# Gimbal_Driveboard.net
KiCad netlist of a schematic drawn in EAGLE
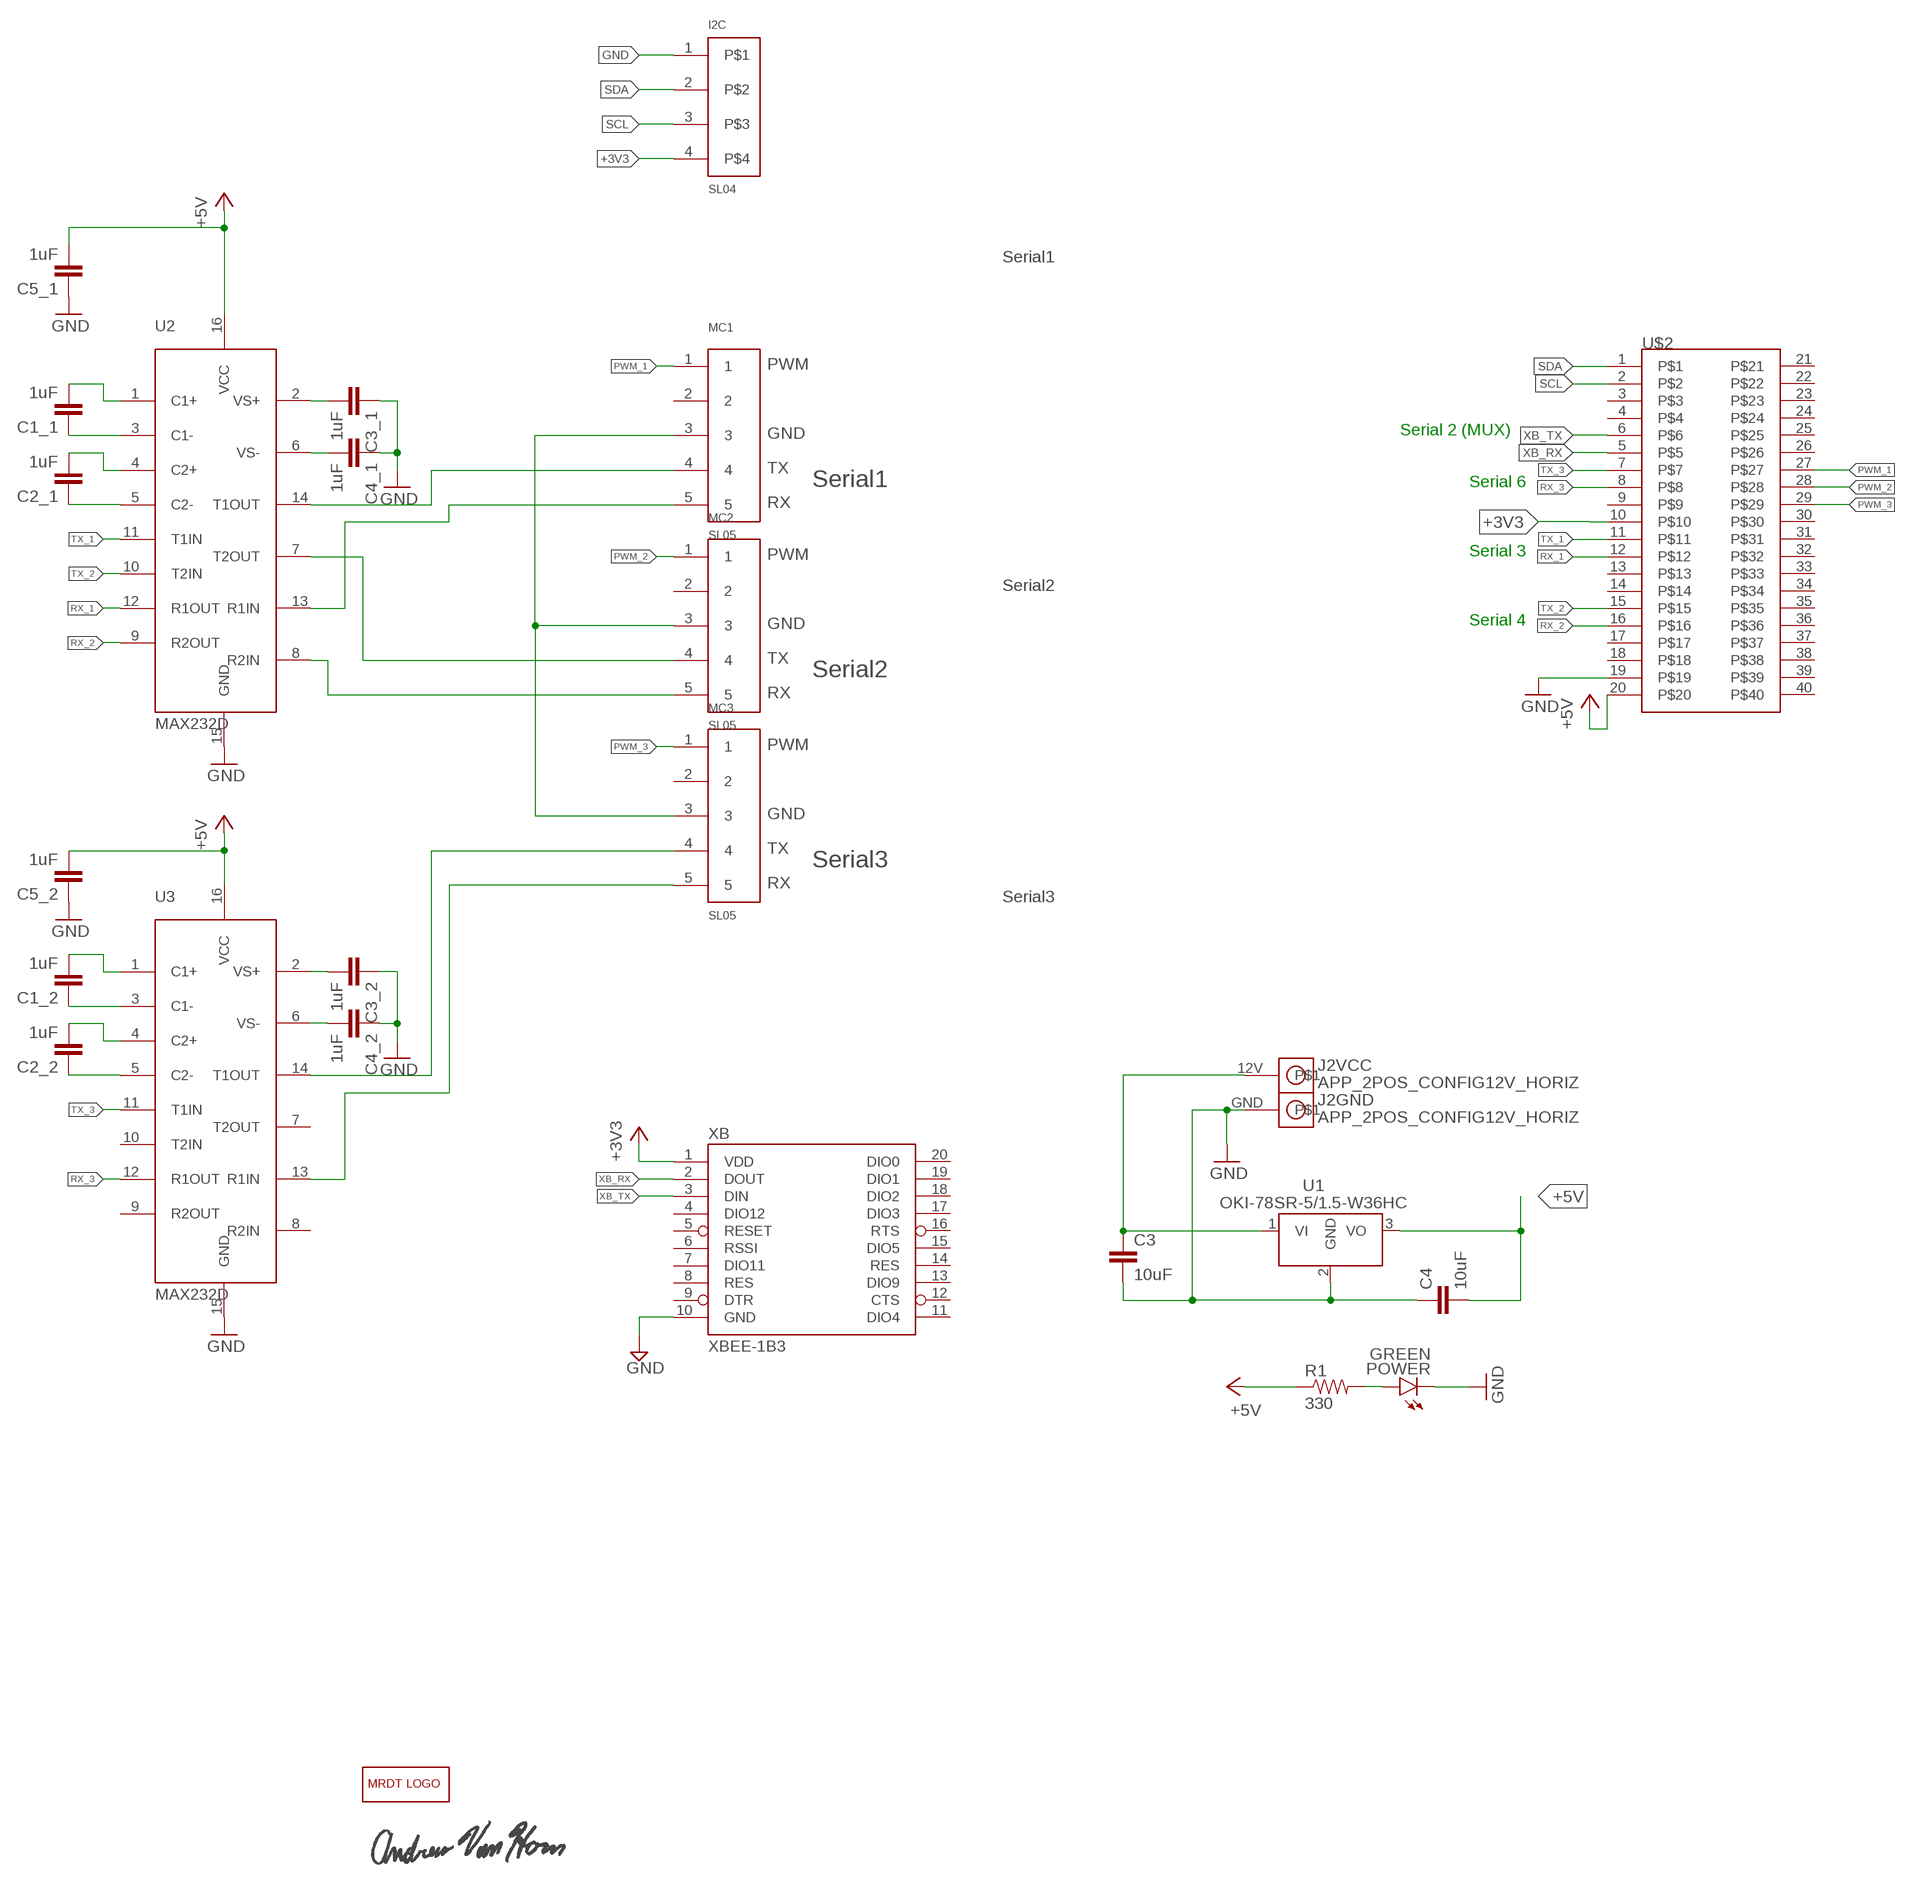
[diagram p0: schematic, sheet 1]

(export (version "E")
  (design (tool "Eeschema 10.0.6"))
  (components
    (comp (ref "C1_1")
      (value "1uF")
      (footprint "eagle-import:0805")
      (libsource (lib "eagle-import") (part "CAP0805"))
    )
    (comp (ref "C1_2")
      (value "1uF")
      (footprint "eagle-import:0805")
      (libsource (lib "eagle-import") (part "CAP0805"))
    )
    (comp (ref "C2_1")
      (value "1uF")
      (footprint "eagle-import:0805")
      (libsource (lib "eagle-import") (part "CAP0805"))
    )
    (comp (ref "C2_2")
      (value "1uF")
      (footprint "eagle-import:0805")
      (libsource (lib "eagle-import") (part "CAP0805"))
    )
    (comp (ref "C3")
      (value "10uF")
      (footprint "eagle-import:0805")
      (libsource (lib "eagle-import") (part "CAP0805"))
    )
    (comp (ref "C3_1")
      (value "1uF")
      (footprint "eagle-import:0805")
      (libsource (lib "eagle-import") (part "CAP0805"))
    )
    (comp (ref "C3_2")
      (value "1uF")
      (footprint "eagle-import:0805")
      (libsource (lib "eagle-import") (part "CAP0805"))
    )
    (comp (ref "C4")
      (value "10uF")
      (footprint "eagle-import:0805")
      (libsource (lib "eagle-import") (part "CAP0805"))
    )
    (comp (ref "C4_1")
      (value "1uF")
      (footprint "eagle-import:0805")
      (libsource (lib "eagle-import") (part "CAP0805"))
    )
    (comp (ref "C4_2")
      (value "1uF")
      (footprint "eagle-import:0805")
      (libsource (lib "eagle-import") (part "CAP0805"))
    )
    (comp (ref "C5_1")
      (value "1uF")
      (footprint "eagle-import:0805")
      (libsource (lib "eagle-import") (part "CAP0805"))
    )
    (comp (ref "C5_2")
      (value "1uF")
      (footprint "eagle-import:0805")
      (libsource (lib "eagle-import") (part "CAP0805"))
    )
    (comp (ref "I2C")
      (value "SL04")
      (footprint "eagle-import:MOLEX_SL_04_TH")
      (libsource (lib "eagle-import") (part "SL04"))
    )
    (comp (ref "J2")
      (value "APP_2POS_CONFIG12V_HORIZ")
      (footprint "eagle-import:APP45_12V_HORIZ_CONFIG")
      (libsource (lib "eagle-import") (part "APP_2POS_CONFIG12V_HORIZ"))
    )
    (comp (ref "LOGO1")
      (value "MRDT_LOGO")
      (footprint "eagle-import:MRDT_LOGO")
      (libsource (lib "eagle-import") (part "MRDT_LOGO"))
    )
    (comp (ref "MC1")
      (value "SL05")
      (footprint "eagle-import:MOLEX_SL_05_TH")
      (libsource (lib "eagle-import") (part "SL05"))
    )
    (comp (ref "MC2")
      (value "SL05")
      (footprint "eagle-import:MOLEX_SL_05_TH")
      (libsource (lib "eagle-import") (part "SL05"))
    )
    (comp (ref "MC3")
      (value "SL05")
      (footprint "eagle-import:MOLEX_SL_05_TH")
      (libsource (lib "eagle-import") (part "SL05"))
    )
    (comp (ref "POWER")
      (value "GREEN")
      (footprint "eagle-import:LED-1206")
      (libsource (lib "eagle-import") (part "LED-GREEN1206"))
    )
    (comp (ref "R1")
      (value "330")
      (footprint "eagle-import:0805")
      (libsource (lib "eagle-import") (part "0.22OHM-1/4W-1%(0805)"))
    )
    (comp (ref "U$2")
      (value "TI_BACKPACK_HEADER")
      (footprint "eagle-import:TI_BACKPACK_HEADER")
      (libsource (lib "eagle-import") (part "TI_BACKPACK_HEADER"))
    )
    (comp (ref "U$3")
      (value "ANDREW_VAN_HORN_SIGNATURE")
      (footprint "eagle-import:ANDREW_VAN_HORN_SIGNATURE")
      (libsource (lib "eagle-import") (part "ANDREW_VAN_HORN_SIGNATURE"))
    )
    (comp (ref "U1")
      (value "OKI-78SR-5/1.5-W36HC")
      (footprint "eagle-import:OKI-78SR_HORIZ")
      (libsource (lib "eagle-import") (part "OKI-78SR-/1.5-W36?CH5"))
    )
    (comp (ref "U2")
      (value "MAX232D")
      (footprint "eagle-import:SOIC16")
      (libsource (lib "eagle-import") (part "MAX232D"))
    )
    (comp (ref "U3")
      (value "MAX232D")
      (footprint "eagle-import:SOIC16")
      (libsource (lib "eagle-import") (part "MAX232D"))
    )
    (comp (ref "XB")
      (value "XBEE-1B3")
      (footprint "eagle-import:XBEE-SMD")
      (libsource (lib "eagle-import") (part "XBEE-1B3"))
    )
  )
  (nets
    (net (code "1") (name "+3V3") (class "Default")
      (node (ref "I2C") (pin "4") (pinfunction "P$4_4") (pintype "bidirectional"))
      (node (ref "U$2") (pin "10") (pinfunction "P$10_10") (pintype "bidirectional"))
      (node (ref "XB") (pin "1") (pinfunction "VDD_1") (pintype "power_in"))
    )
    (net (code "2") (name "+5V") (class "Default")
      (node (ref "C4") (pin "2") (pinfunction "2_2") (pintype "passive"))
      (node (ref "C5_1") (pin "2") (pinfunction "2_2") (pintype "passive"))
      (node (ref "C5_2") (pin "2") (pinfunction "2_2") (pintype "passive"))
      (node (ref "R1") (pin "1") (pinfunction "1_1") (pintype "passive"))
      (node (ref "U$2") (pin "20") (pinfunction "P$20_20") (pintype "bidirectional"))
      (node (ref "U1") (pin "3") (pinfunction "VO_3") (pintype "bidirectional"))
      (node (ref "U2") (pin "16") (pinfunction "VCC_16") (pintype "bidirectional"))
      (node (ref "U3") (pin "16") (pinfunction "VCC_16") (pintype "bidirectional"))
    )
    (net (code "3") (name "GND") (class "Default")
      (node (ref "C3") (pin "2") (pinfunction "2_2") (pintype "passive"))
      (node (ref "C3_1") (pin "1") (pinfunction "1_1") (pintype "passive"))
      (node (ref "C3_2") (pin "1") (pinfunction "1_1") (pintype "passive"))
      (node (ref "C4") (pin "1") (pinfunction "1_1") (pintype "passive"))
      (node (ref "C4_1") (pin "1") (pinfunction "1_1") (pintype "passive"))
      (node (ref "C4_2") (pin "1") (pinfunction "1_1") (pintype "passive"))
      (node (ref "C5_1") (pin "1") (pinfunction "1_1") (pintype "passive"))
      (node (ref "C5_2") (pin "1") (pinfunction "1_1") (pintype "passive"))
      (node (ref "I2C") (pin "1") (pinfunction "P$1_1") (pintype "bidirectional"))
      (node (ref "J2") (pin "GND") (pinfunction "P$1_GND") (pintype "bidirectional"))
      (node (ref "MC1") (pin "3") (pinfunction "3_3") (pintype "bidirectional"))
      (node (ref "MC2") (pin "3") (pinfunction "3_3") (pintype "bidirectional"))
      (node (ref "MC3") (pin "3") (pinfunction "3_3") (pintype "bidirectional"))
      (node (ref "POWER") (pin "C") (pinfunction "C_C") (pintype "passive"))
      (node (ref "U$2") (pin "19") (pinfunction "P$19_19") (pintype "bidirectional"))
      (node (ref "U1") (pin "2") (pinfunction "GND_2") (pintype "bidirectional"))
      (node (ref "U2") (pin "15") (pinfunction "GND_15") (pintype "bidirectional"))
      (node (ref "U3") (pin "15") (pinfunction "GND_15") (pintype "bidirectional"))
      (node (ref "XB") (pin "10") (pinfunction "GND_10") (pintype "power_in"))
    )
    (net (code "4") (name "Net-(J2B-P$1)") (class "Default")
      (node (ref "C3") (pin "1") (pinfunction "1_1") (pintype "passive"))
      (node (ref "J2") (pin "12V") (pinfunction "P$1_12V") (pintype "bidirectional"))
      (node (ref "U1") (pin "1") (pinfunction "VI_1") (pintype "bidirectional"))
    )
    (net (code "5") (name "Net-(POWER-PadA)") (class "Default")
      (node (ref "POWER") (pin "A") (pinfunction "A_A") (pintype "passive"))
      (node (ref "R1") (pin "2") (pinfunction "2_2") (pintype "passive"))
    )
    (net (code "6") (name "Net-(U2-C1+)") (class "Default")
      (node (ref "C1_1") (pin "2") (pinfunction "2_2") (pintype "passive"))
      (node (ref "U2") (pin "1") (pinfunction "C1+_1") (pintype "bidirectional"))
    )
    (net (code "7") (name "Net-(U2-C1-)") (class "Default")
      (node (ref "C1_1") (pin "1") (pinfunction "1_1") (pintype "passive"))
      (node (ref "U2") (pin "3") (pinfunction "C1-_3") (pintype "bidirectional"))
    )
    (net (code "8") (name "Net-(U2-C2+)") (class "Default")
      (node (ref "C2_1") (pin "2") (pinfunction "2_2") (pintype "passive"))
      (node (ref "U2") (pin "4") (pinfunction "C2+_4") (pintype "bidirectional"))
    )
    (net (code "9") (name "Net-(U2-C2-)") (class "Default")
      (node (ref "C2_1") (pin "1") (pinfunction "1_1") (pintype "passive"))
      (node (ref "U2") (pin "5") (pinfunction "C2-_5") (pintype "bidirectional"))
    )
    (net (code "10") (name "Net-(U2-R1IN)") (class "Default")
      (node (ref "MC1") (pin "5") (pinfunction "5_5") (pintype "bidirectional"))
      (node (ref "U2") (pin "13") (pinfunction "R1IN_13") (pintype "bidirectional"))
    )
    (net (code "11") (name "Net-(U2-R2IN)") (class "Default")
      (node (ref "MC2") (pin "5") (pinfunction "5_5") (pintype "bidirectional"))
      (node (ref "U2") (pin "8") (pinfunction "R2IN_8") (pintype "bidirectional"))
    )
    (net (code "12") (name "Net-(U2-T1OUT)") (class "Default")
      (node (ref "MC1") (pin "4") (pinfunction "4_4") (pintype "bidirectional"))
      (node (ref "U2") (pin "14") (pinfunction "T1OUT_14") (pintype "bidirectional"))
    )
    (net (code "13") (name "Net-(U2-T2OUT)") (class "Default")
      (node (ref "MC2") (pin "4") (pinfunction "4_4") (pintype "bidirectional"))
      (node (ref "U2") (pin "7") (pinfunction "T2OUT_7") (pintype "bidirectional"))
    )
    (net (code "14") (name "Net-(U2-VS+)") (class "Default")
      (node (ref "C3_1") (pin "2") (pinfunction "2_2") (pintype "passive"))
      (node (ref "U2") (pin "2") (pinfunction "VS+_2") (pintype "bidirectional"))
    )
    (net (code "15") (name "Net-(U2-VS-)") (class "Default")
      (node (ref "C4_1") (pin "2") (pinfunction "2_2") (pintype "passive"))
      (node (ref "U2") (pin "6") (pinfunction "VS-_6") (pintype "bidirectional"))
    )
    (net (code "16") (name "Net-(U3-C1+)") (class "Default")
      (node (ref "C1_2") (pin "2") (pinfunction "2_2") (pintype "passive"))
      (node (ref "U3") (pin "1") (pinfunction "C1+_1") (pintype "bidirectional"))
    )
    (net (code "17") (name "Net-(U3-C1-)") (class "Default")
      (node (ref "C1_2") (pin "1") (pinfunction "1_1") (pintype "passive"))
      (node (ref "U3") (pin "3") (pinfunction "C1-_3") (pintype "bidirectional"))
    )
    (net (code "18") (name "Net-(U3-C2+)") (class "Default")
      (node (ref "C2_2") (pin "2") (pinfunction "2_2") (pintype "passive"))
      (node (ref "U3") (pin "4") (pinfunction "C2+_4") (pintype "bidirectional"))
    )
    (net (code "19") (name "Net-(U3-C2-)") (class "Default")
      (node (ref "C2_2") (pin "1") (pinfunction "1_1") (pintype "passive"))
      (node (ref "U3") (pin "5") (pinfunction "C2-_5") (pintype "bidirectional"))
    )
    (net (code "20") (name "Net-(U3-R1IN)") (class "Default")
      (node (ref "MC3") (pin "5") (pinfunction "5_5") (pintype "bidirectional"))
      (node (ref "U3") (pin "13") (pinfunction "R1IN_13") (pintype "bidirectional"))
    )
    (net (code "21") (name "Net-(U3-T1OUT)") (class "Default")
      (node (ref "MC3") (pin "4") (pinfunction "4_4") (pintype "bidirectional"))
      (node (ref "U3") (pin "14") (pinfunction "T1OUT_14") (pintype "bidirectional"))
    )
    (net (code "22") (name "Net-(U3-VS+)") (class "Default")
      (node (ref "C3_2") (pin "2") (pinfunction "2_2") (pintype "passive"))
      (node (ref "U3") (pin "2") (pinfunction "VS+_2") (pintype "bidirectional"))
    )
    (net (code "23") (name "Net-(U3-VS-)") (class "Default")
      (node (ref "C4_2") (pin "2") (pinfunction "2_2") (pintype "passive"))
      (node (ref "U3") (pin "6") (pinfunction "VS-_6") (pintype "bidirectional"))
    )
    (net (code "24") (name "PWM_1") (class "Default")
      (node (ref "MC1") (pin "1") (pinfunction "1_1") (pintype "bidirectional"))
      (node (ref "U$2") (pin "27") (pinfunction "P$27_27") (pintype "bidirectional"))
    )
    (net (code "25") (name "PWM_2") (class "Default")
      (node (ref "MC2") (pin "1") (pinfunction "1_1") (pintype "bidirectional"))
      (node (ref "U$2") (pin "28") (pinfunction "P$28_28") (pintype "bidirectional"))
    )
    (net (code "26") (name "PWM_3") (class "Default")
      (node (ref "MC3") (pin "1") (pinfunction "1_1") (pintype "bidirectional"))
      (node (ref "U$2") (pin "29") (pinfunction "P$29_29") (pintype "bidirectional"))
    )
    (net (code "27") (name "RX_1") (class "Default")
      (node (ref "U$2") (pin "12") (pinfunction "P$12_12") (pintype "bidirectional"))
      (node (ref "U2") (pin "12") (pinfunction "R1OUT_12") (pintype "bidirectional"))
    )
    (net (code "28") (name "RX_2") (class "Default")
      (node (ref "U$2") (pin "16") (pinfunction "P$16_16") (pintype "bidirectional"))
      (node (ref "U2") (pin "9") (pinfunction "R2OUT_9") (pintype "bidirectional"))
    )
    (net (code "29") (name "RX_3") (class "Default")
      (node (ref "U$2") (pin "8") (pinfunction "P$8_8") (pintype "bidirectional"))
      (node (ref "U3") (pin "12") (pinfunction "R1OUT_12") (pintype "bidirectional"))
    )
    (net (code "30") (name "SCL") (class "Default")
      (node (ref "I2C") (pin "3") (pinfunction "P$3_3") (pintype "bidirectional"))
      (node (ref "U$2") (pin "2") (pinfunction "P$2_2") (pintype "bidirectional"))
    )
    (net (code "31") (name "SDA") (class "Default")
      (node (ref "I2C") (pin "2") (pinfunction "P$2_2") (pintype "bidirectional"))
      (node (ref "U$2") (pin "1") (pinfunction "P$1_1") (pintype "bidirectional"))
    )
    (net (code "32") (name "TX_1") (class "Default")
      (node (ref "U$2") (pin "11") (pinfunction "P$11_11") (pintype "bidirectional"))
      (node (ref "U2") (pin "11") (pinfunction "T1IN_11") (pintype "bidirectional"))
    )
    (net (code "33") (name "TX_2") (class "Default")
      (node (ref "U$2") (pin "15") (pinfunction "P$15_15") (pintype "bidirectional"))
      (node (ref "U2") (pin "10") (pinfunction "T2IN_10") (pintype "bidirectional"))
    )
    (net (code "34") (name "TX_3") (class "Default")
      (node (ref "U$2") (pin "7") (pinfunction "P$7_7") (pintype "bidirectional"))
      (node (ref "U3") (pin "11") (pinfunction "T1IN_11") (pintype "bidirectional"))
    )
    (net (code "35") (name "XB_RX") (class "Default")
      (node (ref "U$2") (pin "5") (pinfunction "P$5_5") (pintype "bidirectional"))
      (node (ref "XB") (pin "2") (pinfunction "DOUT_2") (pintype "output"))
    )
    (net (code "36") (name "XB_TX") (class "Default")
      (node (ref "U$2") (pin "6") (pinfunction "P$6_6") (pintype "bidirectional"))
      (node (ref "XB") (pin "3") (pinfunction "DIN_3") (pintype "input"))
    )
    (net (code "37") (name "unconnected-(MC1-Pad2)") (class "Default")
      (node (ref "MC1") (pin "2") (pinfunction "2_2") (pintype "bidirectional"))
    )
    (net (code "38") (name "unconnected-(MC2-Pad2)") (class "Default")
      (node (ref "MC2") (pin "2") (pinfunction "2_2") (pintype "bidirectional"))
    )
    (net (code "39") (name "unconnected-(MC3-Pad2)") (class "Default")
      (node (ref "MC3") (pin "2") (pinfunction "2_2") (pintype "bidirectional"))
    )
    (net (code "40") (name "unconnected-(U$2-P$3-Pad3)") (class "Default")
      (node (ref "U$2") (pin "3") (pinfunction "P$3_3") (pintype "bidirectional"))
    )
    (net (code "41") (name "unconnected-(U$2-P$4-Pad4)") (class "Default")
      (node (ref "U$2") (pin "4") (pinfunction "P$4_4") (pintype "bidirectional"))
    )
    (net (code "42") (name "unconnected-(U$2-P$9-Pad9)") (class "Default")
      (node (ref "U$2") (pin "9") (pinfunction "P$9_9") (pintype "bidirectional"))
    )
    (net (code "43") (name "unconnected-(U$2-P$13-Pad13)") (class "Default")
      (node (ref "U$2") (pin "13") (pinfunction "P$13_13") (pintype "bidirectional"))
    )
    (net (code "44") (name "unconnected-(U$2-P$14-Pad14)") (class "Default")
      (node (ref "U$2") (pin "14") (pinfunction "P$14_14") (pintype "bidirectional"))
    )
    (net (code "45") (name "unconnected-(U$2-P$17-Pad17)") (class "Default")
      (node (ref "U$2") (pin "17") (pinfunction "P$17_17") (pintype "bidirectional"))
    )
    (net (code "46") (name "unconnected-(U$2-P$18-Pad18)") (class "Default")
      (node (ref "U$2") (pin "18") (pinfunction "P$18_18") (pintype "bidirectional"))
    )
    (net (code "47") (name "unconnected-(U$2-P$21-Pad21)") (class "Default")
      (node (ref "U$2") (pin "21") (pinfunction "P$21_21") (pintype "bidirectional"))
    )
    (net (code "48") (name "unconnected-(U$2-P$22-Pad22)") (class "Default")
      (node (ref "U$2") (pin "22") (pinfunction "P$22_22") (pintype "bidirectional"))
    )
    (net (code "49") (name "unconnected-(U$2-P$23-Pad23)") (class "Default")
      (node (ref "U$2") (pin "23") (pinfunction "P$23_23") (pintype "bidirectional"))
    )
    (net (code "50") (name "unconnected-(U$2-P$24-Pad24)") (class "Default")
      (node (ref "U$2") (pin "24") (pinfunction "P$24_24") (pintype "bidirectional"))
    )
    (net (code "51") (name "unconnected-(U$2-P$25-Pad25)") (class "Default")
      (node (ref "U$2") (pin "25") (pinfunction "P$25_25") (pintype "bidirectional"))
    )
    (net (code "52") (name "unconnected-(U$2-P$26-Pad26)") (class "Default")
      (node (ref "U$2") (pin "26") (pinfunction "P$26_26") (pintype "bidirectional"))
    )
    (net (code "53") (name "unconnected-(U$2-P$30-Pad30)") (class "Default")
      (node (ref "U$2") (pin "30") (pinfunction "P$30_30") (pintype "bidirectional"))
    )
    (net (code "54") (name "unconnected-(U$2-P$31-Pad31)") (class "Default")
      (node (ref "U$2") (pin "31") (pinfunction "P$31_31") (pintype "bidirectional"))
    )
    (net (code "55") (name "unconnected-(U$2-P$32-Pad32)") (class "Default")
      (node (ref "U$2") (pin "32") (pinfunction "P$32_32") (pintype "bidirectional"))
    )
    (net (code "56") (name "unconnected-(U$2-P$33-Pad33)") (class "Default")
      (node (ref "U$2") (pin "33") (pinfunction "P$33_33") (pintype "bidirectional"))
    )
    (net (code "57") (name "unconnected-(U$2-P$34-Pad34)") (class "Default")
      (node (ref "U$2") (pin "34") (pinfunction "P$34_34") (pintype "bidirectional"))
    )
    (net (code "58") (name "unconnected-(U$2-P$35-Pad35)") (class "Default")
      (node (ref "U$2") (pin "35") (pinfunction "P$35_35") (pintype "bidirectional"))
    )
    (net (code "59") (name "unconnected-(U$2-P$36-Pad36)") (class "Default")
      (node (ref "U$2") (pin "36") (pinfunction "P$36_36") (pintype "bidirectional"))
    )
    (net (code "60") (name "unconnected-(U$2-P$37-Pad37)") (class "Default")
      (node (ref "U$2") (pin "37") (pinfunction "P$37_37") (pintype "bidirectional"))
    )
    (net (code "61") (name "unconnected-(U$2-P$38-Pad38)") (class "Default")
      (node (ref "U$2") (pin "38") (pinfunction "P$38_38") (pintype "bidirectional"))
    )
    (net (code "62") (name "unconnected-(U$2-P$39-Pad39)") (class "Default")
      (node (ref "U$2") (pin "39") (pinfunction "P$39_39") (pintype "bidirectional"))
    )
    (net (code "63") (name "unconnected-(U$2-P$40-Pad40)") (class "Default")
      (node (ref "U$2") (pin "40") (pinfunction "P$40_40") (pintype "bidirectional"))
    )
    (net (code "64") (name "unconnected-(U3-R2IN-Pad8)") (class "Default")
      (node (ref "U3") (pin "8") (pinfunction "R2IN_8") (pintype "bidirectional"))
    )
    (net (code "65") (name "unconnected-(U3-R2OUT-Pad9)") (class "Default")
      (node (ref "U3") (pin "9") (pinfunction "R2OUT_9") (pintype "bidirectional"))
    )
    (net (code "66") (name "unconnected-(U3-T2IN-Pad10)") (class "Default")
      (node (ref "U3") (pin "10") (pinfunction "T2IN_10") (pintype "bidirectional"))
    )
    (net (code "67") (name "unconnected-(U3-T2OUT-Pad7)") (class "Default")
      (node (ref "U3") (pin "7") (pinfunction "T2OUT_7") (pintype "bidirectional"))
    )
    (net (code "68") (name "unconnected-(XB-CTS-Pad12)") (class "Default")
      (node (ref "XB") (pin "12") (pinfunction "CTS_12") (pintype "output"))
    )
    (net (code "69") (name "unconnected-(XB-DIO0-Pad20)") (class "Default")
      (node (ref "XB") (pin "20") (pinfunction "DIO0_20") (pintype "bidirectional"))
    )
    (net (code "70") (name "unconnected-(XB-DIO1-Pad19)") (class "Default")
      (node (ref "XB") (pin "19") (pinfunction "DIO1_19") (pintype "bidirectional"))
    )
    (net (code "71") (name "unconnected-(XB-DIO2-Pad18)") (class "Default")
      (node (ref "XB") (pin "18") (pinfunction "DIO2_18") (pintype "bidirectional"))
    )
    (net (code "72") (name "unconnected-(XB-DIO3-Pad17)") (class "Default")
      (node (ref "XB") (pin "17") (pinfunction "DIO3_17") (pintype "bidirectional"))
    )
    (net (code "73") (name "unconnected-(XB-DIO4-Pad11)") (class "Default")
      (node (ref "XB") (pin "11") (pinfunction "DIO4_11") (pintype "bidirectional"))
    )
    (net (code "74") (name "unconnected-(XB-DIO5-Pad15)") (class "Default")
      (node (ref "XB") (pin "15") (pinfunction "DIO5_15") (pintype "bidirectional"))
    )
    (net (code "75") (name "unconnected-(XB-DIO9-Pad13)") (class "Default")
      (node (ref "XB") (pin "13") (pinfunction "DIO9_13") (pintype "bidirectional"))
    )
    (net (code "76") (name "unconnected-(XB-DIO11-Pad7)") (class "Default")
      (node (ref "XB") (pin "7") (pinfunction "DIO11_7") (pintype "bidirectional"))
    )
    (net (code "77") (name "unconnected-(XB-DIO12-Pad4)") (class "Default")
      (node (ref "XB") (pin "4") (pinfunction "DIO12_4") (pintype "bidirectional"))
    )
    (net (code "78") (name "unconnected-(XB-DTR-Pad9)") (class "Default")
      (node (ref "XB") (pin "9") (pinfunction "DTR_9") (pintype "bidirectional"))
    )
    (net (code "79") (name "unconnected-(XB-RES-Pad8)") (class "Default")
      (node (ref "XB") (pin "8") (pinfunction "RES_8") (pintype "bidirectional"))
    )
    (net (code "80") (name "unconnected-(XB-RES-Pad14)") (class "Default")
      (node (ref "XB") (pin "14") (pinfunction "RES_14") (pintype "bidirectional"))
    )
    (net (code "81") (name "unconnected-(XB-RESET-Pad5)") (class "Default")
      (node (ref "XB") (pin "5") (pinfunction "RESET_5") (pintype "input"))
    )
    (net (code "82") (name "unconnected-(XB-RSSI-Pad6)") (class "Default")
      (node (ref "XB") (pin "6") (pinfunction "RSSI_6") (pintype "bidirectional"))
    )
    (net (code "83") (name "unconnected-(XB-RTS-Pad16)") (class "Default")
      (node (ref "XB") (pin "16") (pinfunction "RTS_16") (pintype "input"))
    )
  )
)
